# ohm4_ocxo.net
KiCad netlist of a schematic drawn in EAGLE
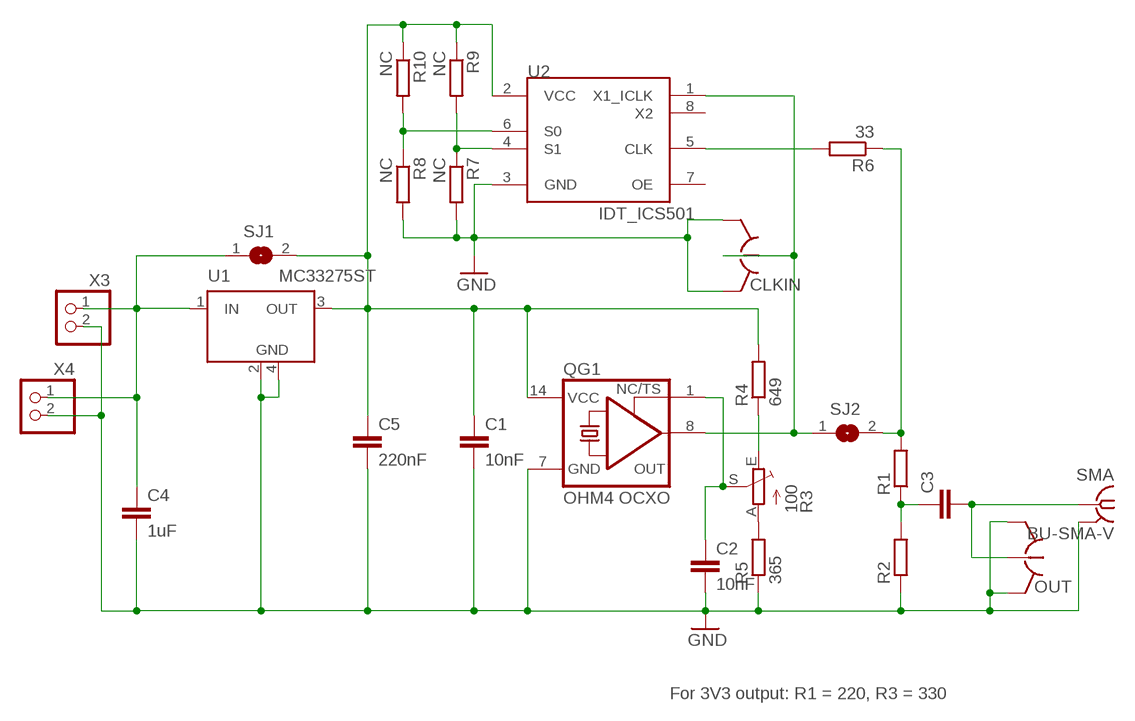
[diagram p0: schematic, sheet 1]

(export (version "E")
  (design (tool "Eeschema 10.0.6"))
  (components
    (comp (ref "C1")
      (value "10nF")
      (footprint "eagle-import:C0603")
      (libsource (lib "eagle-import") (part "C-EUC0603"))
    )
    (comp (ref "C2")
      (value "10nF")
      (footprint "eagle-import:C0603")
      (libsource (lib "eagle-import") (part "C-EUC0603"))
    )
    (comp (ref "C3")
      (value "C-EUC0603")
      (footprint "eagle-import:C0603")
      (libsource (lib "eagle-import") (part "C-EUC0603"))
    )
    (comp (ref "C4")
      (value "1uF")
      (footprint "eagle-import:C0603")
      (libsource (lib "eagle-import") (part "C-EUC0603"))
    )
    (comp (ref "C5")
      (value "220nF")
      (footprint "eagle-import:C0603")
      (libsource (lib "eagle-import") (part "C-EUC0603"))
    )
    (comp (ref "CLKIN")
      (value "HRS_UFL")
      (footprint "eagle-import:HRS_UFL")
      (libsource (lib "eagle-import") (part "HRS_UFL"))
    )
    (comp (ref "OUT")
      (value "HRS_UFL")
      (footprint "eagle-import:HRS_UFL")
      (libsource (lib "eagle-import") (part "HRS_UFL"))
    )
    (comp (ref "QG1")
      (value "OHM4 OCXO")
      (footprint "eagle-import:DIL14S")
      (libsource (lib "eagle-import") (part "XO-14"))
    )
    (comp (ref "R1")
      (value "R-EU_R0603")
      (footprint "eagle-import:R0603")
      (libsource (lib "eagle-import") (part "R-EU_R0603"))
    )
    (comp (ref "R2")
      (value "R-EU_R0603")
      (footprint "eagle-import:R0603")
      (libsource (lib "eagle-import") (part "R-EU_R0603"))
    )
    (comp (ref "R3")
      (value "100")
      (footprint "eagle-import:PT-SPIN")
      (libsource (lib "eagle-import") (part "TRIM_EU-PTSPIN"))
    )
    (comp (ref "R4")
      (value "649")
      (footprint "eagle-import:R0603")
      (libsource (lib "eagle-import") (part "R-EU_R0603"))
    )
    (comp (ref "R5")
      (value "365")
      (footprint "eagle-import:R0603")
      (libsource (lib "eagle-import") (part "R-EU_R0603"))
    )
    (comp (ref "R6")
      (value "33")
      (footprint "eagle-import:R0603")
      (libsource (lib "eagle-import") (part "R-EU_R0603"))
    )
    (comp (ref "R7")
      (value "NC")
      (footprint "eagle-import:R0603")
      (libsource (lib "eagle-import") (part "R-EU_R0603"))
    )
    (comp (ref "R8")
      (value "NC")
      (footprint "eagle-import:R0603")
      (libsource (lib "eagle-import") (part "R-EU_R0603"))
    )
    (comp (ref "R9")
      (value "NC")
      (footprint "eagle-import:R0603")
      (libsource (lib "eagle-import") (part "R-EU_R0603"))
    )
    (comp (ref "R10")
      (value "NC")
      (footprint "eagle-import:R0603")
      (libsource (lib "eagle-import") (part "R-EU_R0603"))
    )
    (comp (ref "SJ1") (value "SJ") (footprint "eagle-import:SJ") (libsource (lib "eagle-import") (part "SJ")))
    (comp (ref "SJ2") (value "SJ") (footprint "eagle-import:SJ") (libsource (lib "eagle-import") (part "SJ")))
    (comp (ref "SMA")
      (value "BU-SMA-V")
      (footprint "eagle-import:BU-SMA-V")
      (libsource (lib "eagle-import") (part "BU-SMA-V"))
    )
    (comp (ref "U1")
      (value "MC33275ST")
      (footprint "eagle-import:SOT223")
      (libsource (lib "eagle-import") (part "MC33275ST"))
    )
    (comp (ref "U2")
      (value "IDT_ICS501")
      (footprint "eagle-import:SOIC08")
      (libsource (lib "eagle-import") (part "IDT_ICS501"))
    )
    (comp (ref "X3")
      (value "PINHD-1X2")
      (footprint "eagle-import:1X02")
      (libsource (lib "eagle-import") (part "PINHD-1X2"))
    )
    (comp (ref "X4")
      (value "PINHD-1X2")
      (footprint "eagle-import:1X02")
      (libsource (lib "eagle-import") (part "PINHD-1X2"))
    )
  )
  (nets
    (net (code "1") (name "GND") (class "Default")
      (node (ref "C1") (pin "2") (pinfunction "2_2") (pintype "passive"))
      (node (ref "C2") (pin "2") (pinfunction "2_2") (pintype "passive"))
      (node (ref "C4") (pin "2") (pinfunction "2_2") (pintype "passive"))
      (node (ref "C5") (pin "2") (pinfunction "2_2") (pintype "passive"))
      (node (ref "CLKIN") (pin "GND@1") (pinfunction "GND_GND@1") (pintype "power_in"))
      (node (ref "CLKIN") (pin "GND@2") (pinfunction "GND_GND@2") (pintype "power_in"))
      (node (ref "OUT") (pin "GND@1") (pinfunction "GND_GND@1") (pintype "power_in"))
      (node (ref "OUT") (pin "GND@2") (pinfunction "GND_GND@2") (pintype "power_in"))
      (node (ref "QG1") (pin "7") (pinfunction "GND_7") (pintype "power_in"))
      (node (ref "R2") (pin "1") (pinfunction "1_1") (pintype "passive"))
      (node (ref "R5") (pin "1") (pinfunction "1_1") (pintype "passive"))
      (node (ref "R7") (pin "2") (pinfunction "2_2") (pintype "passive"))
      (node (ref "R8") (pin "2") (pinfunction "2_2") (pintype "passive"))
      (node (ref "SMA") (pin "2") (pinfunction "GND_2") (pintype "power_in"))
      (node (ref "U1") (pin "2") (pinfunction "GND_2") (pintype "power_in"))
      (node (ref "U1") (pin "4") (pinfunction "GND1_4") (pintype "power_in"))
      (node (ref "U2") (pin "3") (pinfunction "GND_3") (pintype "passive"))
      (node (ref "X3") (pin "2") (pinfunction "2_2") (pintype "passive"))
      (node (ref "X4") (pin "2") (pinfunction "2_2") (pintype "passive"))
    )
    (net (code "2") (name "Net-(C3-Pad1)") (class "Default")
      (node (ref "C3") (pin "1") (pinfunction "1_1") (pintype "passive"))
      (node (ref "R1") (pin "1") (pinfunction "1_1") (pintype "passive"))
      (node (ref "R2") (pin "2") (pinfunction "2_2") (pintype "passive"))
    )
    (net (code "3") (name "Net-(CLKIN-1)") (class "Default")
      (node (ref "CLKIN") (pin "SIG") (pinfunction "1_SIG") (pintype "passive"))
      (node (ref "QG1") (pin "8") (pinfunction "OUT_8") (pintype "output"))
      (node (ref "SJ2") (pin "1") (pinfunction "1_1") (pintype "passive"))
      (node (ref "U2") (pin "1") (pinfunction "X1_ICLK_1") (pintype "input"))
    )
    (net (code "4") (name "Net-(OUT-1)") (class "Default")
      (node (ref "C3") (pin "2") (pinfunction "2_2") (pintype "passive"))
      (node (ref "OUT") (pin "SIG") (pinfunction "1_SIG") (pintype "passive"))
      (node (ref "SMA") (pin "1") (pinfunction "1_1") (pintype "passive"))
    )
    (net (code "5") (name "Net-(QG1-TS)") (class "Default")
      (node (ref "C2") (pin "1") (pinfunction "1_1") (pintype "passive"))
      (node (ref "QG1") (pin "1") (pinfunction "TS_1") (pintype "passive"))
      (node (ref "R3") (pin "S") (pinfunction "S_S") (pintype "passive"))
    )
    (net (code "6") (name "Net-(QG1-VCC)") (class "Default")
      (node (ref "C1") (pin "1") (pinfunction "1_1") (pintype "passive"))
      (node (ref "C5") (pin "1") (pinfunction "1_1") (pintype "passive"))
      (node (ref "QG1") (pin "14") (pinfunction "VCC_14") (pintype "power_in"))
      (node (ref "R10") (pin "1") (pinfunction "1_1") (pintype "passive"))
      (node (ref "R4") (pin "2") (pinfunction "2_2") (pintype "passive"))
      (node (ref "R9") (pin "1") (pinfunction "1_1") (pintype "passive"))
      (node (ref "SJ1") (pin "2") (pinfunction "2_2") (pintype "passive"))
      (node (ref "U1") (pin "3") (pinfunction "OUT_3") (pintype "passive"))
      (node (ref "U2") (pin "2") (pinfunction "VCC_2") (pintype "power_in"))
    )
    (net (code "7") (name "Net-(R1-Pad2)") (class "Default")
      (node (ref "R1") (pin "2") (pinfunction "2_2") (pintype "passive"))
      (node (ref "R6") (pin "1") (pinfunction "1_1") (pintype "passive"))
      (node (ref "SJ2") (pin "2") (pinfunction "2_2") (pintype "passive"))
    )
    (net (code "8") (name "Net-(R3-PadA)") (class "Default")
      (node (ref "R3") (pin "A") (pinfunction "A_A") (pintype "passive"))
      (node (ref "R5") (pin "2") (pinfunction "2_2") (pintype "passive"))
    )
    (net (code "9") (name "Net-(R3-PadE)") (class "Default")
      (node (ref "R3") (pin "E") (pinfunction "E_E") (pintype "passive"))
      (node (ref "R4") (pin "1") (pinfunction "1_1") (pintype "passive"))
    )
    (net (code "10") (name "Net-(U1-IN)") (class "Default")
      (node (ref "C4") (pin "1") (pinfunction "1_1") (pintype "passive"))
      (node (ref "SJ1") (pin "1") (pinfunction "1_1") (pintype "passive"))
      (node (ref "U1") (pin "1") (pinfunction "IN_1") (pintype "input"))
      (node (ref "X3") (pin "1") (pinfunction "1_1") (pintype "passive"))
      (node (ref "X4") (pin "1") (pinfunction "1_1") (pintype "passive"))
    )
    (net (code "11") (name "Net-(U2-CLK)") (class "Default")
      (node (ref "R6") (pin "2") (pinfunction "2_2") (pintype "passive"))
      (node (ref "U2") (pin "5") (pinfunction "CLK_5") (pintype "output"))
    )
    (net (code "12") (name "Net-(U2-S0)") (class "Default")
      (node (ref "R10") (pin "2") (pinfunction "2_2") (pintype "passive"))
      (node (ref "R8") (pin "1") (pinfunction "1_1") (pintype "passive"))
      (node (ref "U2") (pin "6") (pinfunction "S0_6") (pintype "input"))
    )
    (net (code "13") (name "Net-(U2-S1)") (class "Default")
      (node (ref "R7") (pin "1") (pinfunction "1_1") (pintype "passive"))
      (node (ref "R9") (pin "2") (pinfunction "2_2") (pintype "passive"))
      (node (ref "U2") (pin "4") (pinfunction "S1_4") (pintype "input"))
    )
    (net (code "14") (name "unconnected-(U2-OE-Pad7)") (class "Default")
      (node (ref "U2") (pin "7") (pinfunction "OE_7") (pintype "input"))
    )
    (net (code "15") (name "unconnected-(U2-X2-Pad8)") (class "Default")
      (node (ref "U2") (pin "8") (pinfunction "X2_8") (pintype "output"))
    )
  )
)
